# PCB_with_nRF_DUAL_Labeled.net
KiCad netlist of a schematic drawn in EAGLE
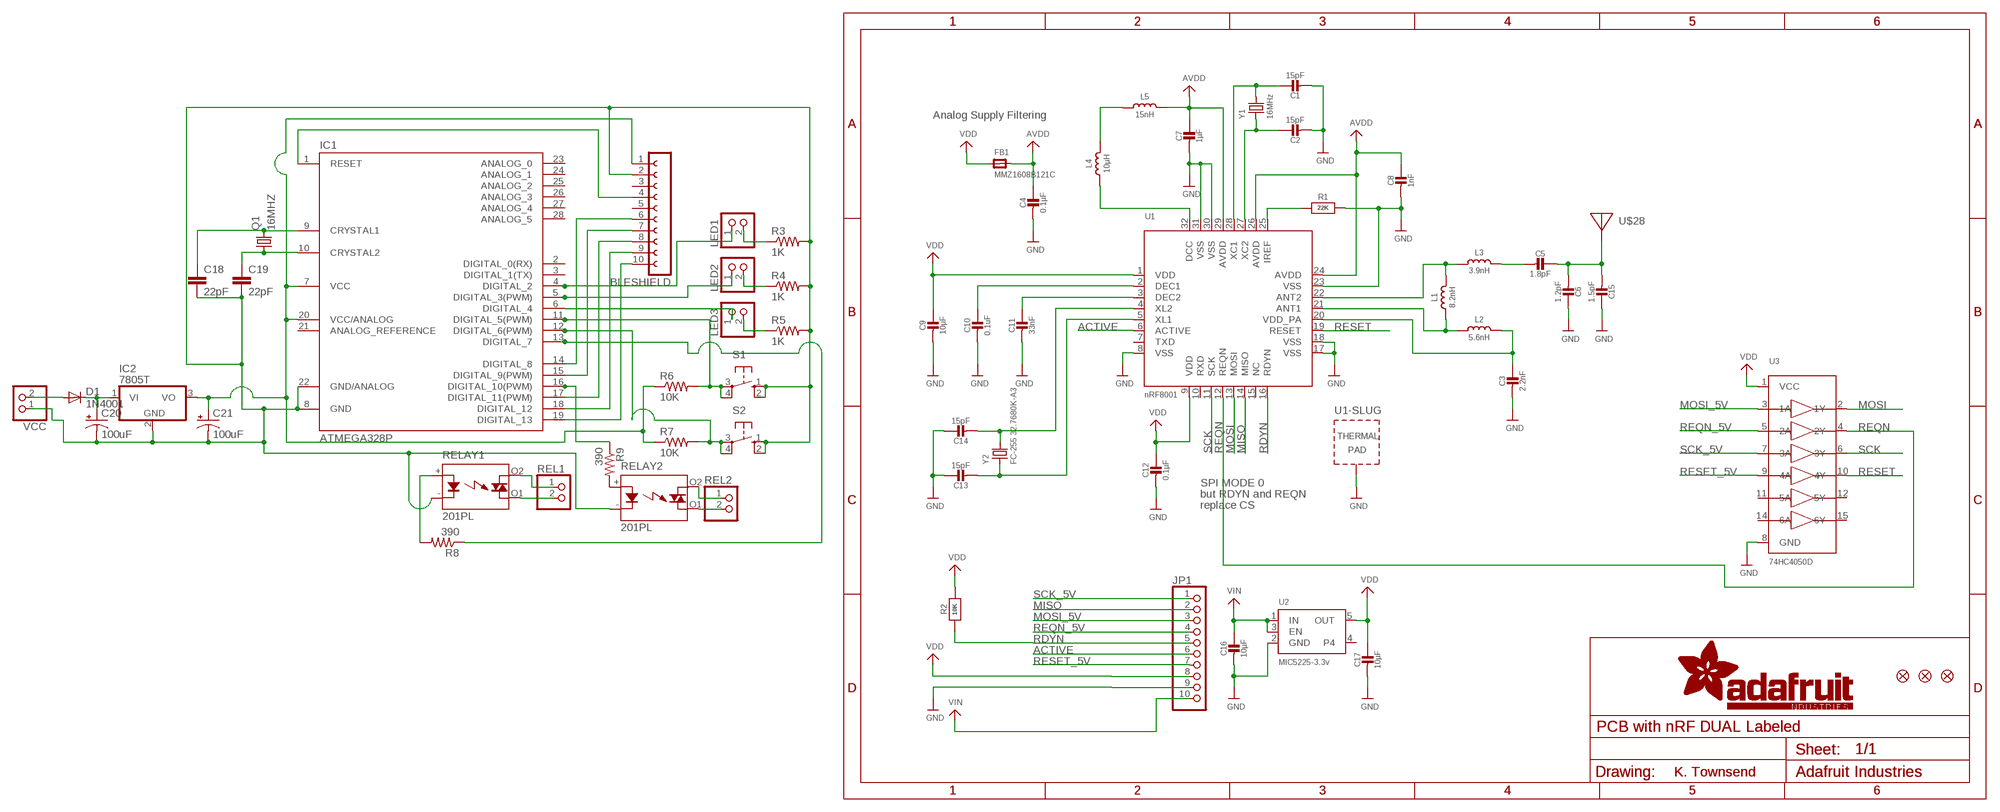
[diagram p0: schematic, sheet 1]

(export (version "E")
  (design (tool "Eeschema 10.0.6"))
  (components
    (comp (ref "BLESHIELD")
      (value "FE10-1")
      (footprint "eagle-import:FE10")
      (libsource (lib "eagle-import") (part "FE10-1"))
    )
    (comp (ref "C1")
      (value "15pF")
      (footprint "eagle-import:0805-NO")
      (libsource (lib "eagle-import") (part "CAP_CERAMIC0805-NOOUTLINE"))
    )
    (comp (ref "C2")
      (value "15pF")
      (footprint "eagle-import:0805-NO")
      (libsource (lib "eagle-import") (part "CAP_CERAMIC0805-NOOUTLINE"))
    )
    (comp (ref "C3")
      (value "2.2nF")
      (footprint "eagle-import:_0402")
      (libsource (lib "eagle-import") (part "CAP_CERAMIC_0402"))
    )
    (comp (ref "C4")
      (value "0.1µF")
      (footprint "eagle-import:0805-NO")
      (libsource (lib "eagle-import") (part "CAP_CERAMIC0805-NOOUTLINE"))
    )
    (comp (ref "C5")
      (value "1.8pF")
      (footprint "eagle-import:_0402MP")
      (libsource (lib "eagle-import") (part "CAP_CERAMIC_0402MP"))
    )
    (comp (ref "C6")
      (value "1.2pF")
      (footprint "eagle-import:_0402MP")
      (libsource (lib "eagle-import") (part "CAP_CERAMIC_0402MP"))
    )
    (comp (ref "C7")
      (value "1µF")
      (footprint "eagle-import:0805-NO")
      (libsource (lib "eagle-import") (part "CAP_CERAMIC0805-NOOUTLINE"))
    )
    (comp (ref "C8")
      (value "1nF")
      (footprint "eagle-import:_0603")
      (libsource (lib "eagle-import") (part "CAP_CERAMIC_0603"))
    )
    (comp (ref "C9")
      (value "10µF")
      (footprint "eagle-import:0805-NO")
      (libsource (lib "eagle-import") (part "CAP_CERAMIC0805-NOOUTLINE"))
    )
    (comp (ref "C10")
      (value "0.1uF")
      (footprint "eagle-import:0805-NO")
      (libsource (lib "eagle-import") (part "CAP_CERAMIC0805-NOOUTLINE"))
    )
    (comp (ref "C11")
      (value "33nF")
      (footprint "eagle-import:0805-NO")
      (libsource (lib "eagle-import") (part "CAP_CERAMIC0805-NOOUTLINE"))
    )
    (comp (ref "C12")
      (value "0.1µF")
      (footprint "eagle-import:0805-NO")
      (libsource (lib "eagle-import") (part "CAP_CERAMIC0805-NOOUTLINE"))
    )
    (comp (ref "C13")
      (value "15pF")
      (footprint "eagle-import:0805-NO")
      (libsource (lib "eagle-import") (part "CAP_CERAMIC0805-NOOUTLINE"))
    )
    (comp (ref "C14")
      (value "15pF")
      (footprint "eagle-import:0805-NO")
      (libsource (lib "eagle-import") (part "CAP_CERAMIC0805-NOOUTLINE"))
    )
    (comp (ref "C15")
      (value "1.5pF")
      (footprint "eagle-import:_0402MP")
      (libsource (lib "eagle-import") (part "CAP_CERAMIC_0402MP"))
    )
    (comp (ref "C16")
      (value "10µF")
      (footprint "eagle-import:0805-NO")
      (libsource (lib "eagle-import") (part "CAP_CERAMIC0805-NOOUTLINE"))
    )
    (comp (ref "C17")
      (value "10µF")
      (footprint "eagle-import:0805-NO")
      (libsource (lib "eagle-import") (part "CAP_CERAMIC0805-NOOUTLINE"))
    )
    (comp (ref "C18")
      (value "22pF")
      (footprint "eagle-import:C025-030X050")
      (libsource (lib "eagle-import") (part "C-EU025-030X050"))
    )
    (comp (ref "C19")
      (value "22pF")
      (footprint "eagle-import:C025-030X050")
      (libsource (lib "eagle-import") (part "C-EU025-030X050"))
    )
    (comp (ref "C20")
      (value "100uF")
      (footprint "eagle-import:E2,5-6")
      (libsource (lib "eagle-import") (part "CPOL-USE2.5-6"))
    )
    (comp (ref "C21")
      (value "100uF")
      (footprint "eagle-import:E2,5-6")
      (libsource (lib "eagle-import") (part "CPOL-USE2.5-6"))
    )
    (comp (ref "D1")
      (value "1N4001")
      (footprint "eagle-import:DO41-10")
      (libsource (lib "eagle-import") (part "1N4004"))
    )
    (comp (ref "FB1")
      (value "MMZ1608B121C")
      (footprint "eagle-import:0805")
      (libsource (lib "eagle-import") (part "FERRITE0805"))
    )
    (comp (ref "FID1")
      (value "FIDUCIAL\"\"")
      (footprint "eagle-import:FIDUCIAL_1MM")
      (libsource (lib "eagle-import") (part "FIDUCIAL{dblquote}{dblquote}"))
    )
    (comp (ref "FID2")
      (value "FIDUCIAL\"\"")
      (footprint "eagle-import:FIDUCIAL_1MM")
      (libsource (lib "eagle-import") (part "FIDUCIAL{dblquote}{dblquote}"))
    )
    (comp (ref "FID3")
      (value "FIDUCIAL\"\"")
      (footprint "eagle-import:FIDUCIAL_1MM")
      (fields (field (name "BOM") "EXCLUDE"))
      (libsource (lib "eagle-import") (part "FIDUCIAL{dblquote}{dblquote}"))
    )
    (comp (ref "IC1")
      (value "ATMEGA328P")
      (footprint "eagle-import:DIL28-3")
      (libsource (lib "eagle-import") (part "ATMEGA168-PU"))
    )
    (comp (ref "IC2")
      (value "7805T")
      (footprint "eagle-import:TO220H")
      (libsource (lib "eagle-import") (part "78T05"))
    )
    (comp (ref "JP1")
      (value "HEADER-1X1070MIL")
      (footprint "eagle-import:1X10_ROUND70")
      (libsource (lib "eagle-import") (part "HEADER-1X1070MIL"))
    )
    (comp (ref "L1")
      (value "8.2nH")
      (footprint "eagle-import:_0402")
      (libsource (lib "eagle-import") (part "INDUCTOR_0402"))
    )
    (comp (ref "L2")
      (value "5.6nH")
      (footprint "eagle-import:_0402")
      (libsource (lib "eagle-import") (part "INDUCTOR_0402"))
    )
    (comp (ref "L3")
      (value "3.9nH")
      (footprint "eagle-import:_0402")
      (libsource (lib "eagle-import") (part "INDUCTOR_0402"))
    )
    (comp (ref "L4")
      (value "10µH")
      (footprint "eagle-import:_0603")
      (libsource (lib "eagle-import") (part "INDUCTOR_0603"))
    )
    (comp (ref "L5")
      (value "15nH")
      (footprint "eagle-import:_0603")
      (libsource (lib "eagle-import") (part "INDUCTOR_0603"))
    )
    (comp (ref "LED1")
      (value "PINHD-1X2")
      (footprint "eagle-import:1X02")
      (libsource (lib "eagle-import") (part "PINHD-1X2"))
    )
    (comp (ref "LED2")
      (value "PINHD-1X2")
      (footprint "eagle-import:1X02")
      (libsource (lib "eagle-import") (part "PINHD-1X2"))
    )
    (comp (ref "LED3")
      (value "PINHD-1X2")
      (footprint "eagle-import:1X02")
      (libsource (lib "eagle-import") (part "PINHD-1X2"))
    )
    (comp (ref "Q1")
      (value "16MHZ")
      (footprint "eagle-import:HC49_S")
      (libsource (lib "eagle-import") (part "CRYSTALHC49S"))
    )
    (comp (ref "R1")
      (value "22K")
      (footprint "eagle-import:_0805MP")
      (libsource (lib "eagle-import") (part "RESISTOR_0805MP"))
    )
    (comp (ref "R2")
      (value "10K")
      (footprint "eagle-import:0805-NO")
      (libsource (lib "eagle-import") (part "RESISTOR0805_NOOUTLINE"))
    )
    (comp (ref "R3")
      (value "1K")
      (footprint "eagle-import:0204_5")
      (libsource (lib "eagle-import") (part "R-US_0204/5"))
    )
    (comp (ref "R4")
      (value "1K")
      (footprint "eagle-import:0204_5")
      (libsource (lib "eagle-import") (part "R-US_0204/5"))
    )
    (comp (ref "R5")
      (value "1K")
      (footprint "eagle-import:0204_5")
      (libsource (lib "eagle-import") (part "R-US_0204/5"))
    )
    (comp (ref "R6")
      (value "10K")
      (footprint "eagle-import:0204_5")
      (libsource (lib "eagle-import") (part "R-US_0204/5"))
    )
    (comp (ref "R7")
      (value "10K")
      (footprint "eagle-import:0204_5")
      (libsource (lib "eagle-import") (part "R-US_0204/5"))
    )
    (comp (ref "R8")
      (value "390")
      (footprint "eagle-import:0204_5")
      (libsource (lib "eagle-import") (part "R-US_0204/5"))
    )
    (comp (ref "R9")
      (value "390")
      (footprint "eagle-import:0204_5")
      (libsource (lib "eagle-import") (part "R-US_0204/5"))
    )
    (comp (ref "REL1")
      (value "PINHD-1X2")
      (footprint "eagle-import:1X02")
      (libsource (lib "eagle-import") (part "PINHD-1X2"))
    )
    (comp (ref "REL2")
      (value "PINHD-1X2")
      (footprint "eagle-import:1X02")
      (libsource (lib "eagle-import") (part "PINHD-1X2"))
    )
    (comp (ref "RELAY1")
      (value "201PL")
      (footprint "eagle-import:AQG")
      (fields (field (name "MF") "AROMAT/ MATSUSHITA") (field (name "MPN") "AQG12105"))
      (libsource (lib "eagle-import") (part "AQG12105"))
    )
    (comp (ref "RELAY2")
      (value "201PL")
      (footprint "eagle-import:AQG")
      (fields (field (name "MF") "AROMAT/ MATSUSHITA") (field (name "MPN") "AQG12105"))
      (libsource (lib "eagle-import") (part "AQG12105"))
    )
    (comp (ref "S1")
      (value "10-XX")
      (footprint "eagle-import:B3F-10XX")
      (fields (field (name "MPN") "B3F-1000"))
      (libsource (lib "eagle-import") (part "10-XX"))
    )
    (comp (ref "S2")
      (value "10-XX")
      (footprint "eagle-import:B3F-10XX")
      (fields (field (name "MPN") "B3F-1000"))
      (libsource (lib "eagle-import") (part "10-XX"))
    )
    (comp (ref "U$28")
      (value "ANTENNA_PCBNRF8001_1.6MM")
      (footprint "eagle-import:ANT_PCB_2.4GHZ_NRF8001_1.6MM_1OZ")
      (libsource (lib "eagle-import") (part "ANTENNA_PCBNRF8001_1.6MM"))
    )
    (comp (ref "U1")
      (value "nRF8001")
      (footprint "eagle-import:QFN32_5MM")
      (libsource (lib "eagle-import") (part "NRF8001"))
    )
    (comp (ref "U2")
      (value "MIC5225-3.3v")
      (footprint "eagle-import:SOT23-5")
      (libsource (lib "eagle-import") (part "VREG_SOT23-5"))
    )
    (comp (ref "U3")
      (value "74HC4050D")
      (footprint "eagle-import:TSSOP16")
      (libsource (lib "eagle-import") (part "74HC4050DTSSOP"))
    )
    (comp (ref "VCC")
      (value "PINHD-1X2")
      (footprint "eagle-import:1X02")
      (libsource (lib "eagle-import") (part "PINHD-1X2"))
    )
    (comp (ref "Y1")
      (value "16MHz")
      (footprint "eagle-import:CRYSTAL_2.5X2")
      (libsource (lib "eagle-import") (part "CRYSTAL2.5X2.0"))
    )
    (comp (ref "Y2")
      (value "FC-255 32.7680K-A3")
      (footprint "eagle-import:CRYSTAL_4.9X1.8")
      (libsource (lib "eagle-import") (part "CRYSTAL4.9X1.8"))
    )
  )
  (nets
    (net (code "1") (name "/ACTIVE") (class "Default")
      (node (ref "JP1") (pin "6") (pinfunction "6_6") (pintype "passive"))
      (node (ref "U1") (pin "6") (pinfunction "ACTIVE_6") (pintype "output"))
    )
    (net (code "2") (name "/MISO") (class "Default")
      (node (ref "JP1") (pin "2") (pinfunction "2_2") (pintype "passive"))
      (node (ref "U1") (pin "14") (pinfunction "MISO_14") (pintype "output"))
    )
    (net (code "3") (name "/MOSI") (class "Default")
      (node (ref "U1") (pin "13") (pinfunction "MOSI_13") (pintype "input"))
      (node (ref "U3") (pin "2") (pinfunction "1Y_2") (pintype "bidirectional"))
    )
    (net (code "4") (name "/MOSI_5V") (class "Default")
      (node (ref "JP1") (pin "3") (pinfunction "3_3") (pintype "passive"))
      (node (ref "U3") (pin "3") (pinfunction "1A_3") (pintype "bidirectional"))
    )
    (net (code "5") (name "/RDYN") (class "Default")
      (node (ref "JP1") (pin "5") (pinfunction "5_5") (pintype "passive"))
      (node (ref "R2") (pin "1") (pinfunction "1_1") (pintype "passive"))
      (node (ref "U1") (pin "16") (pinfunction "RDYN_16") (pintype "output"))
    )
    (net (code "6") (name "/REQN") (class "Default")
      (node (ref "U1") (pin "12") (pinfunction "REQN_12") (pintype "input"))
      (node (ref "U3") (pin "4") (pinfunction "2Y_4") (pintype "bidirectional"))
    )
    (net (code "7") (name "/REQN_5V") (class "Default")
      (node (ref "JP1") (pin "4") (pinfunction "4_4") (pintype "passive"))
      (node (ref "U3") (pin "5") (pinfunction "2A_5") (pintype "bidirectional"))
    )
    (net (code "8") (name "/RESET") (class "Default")
      (node (ref "U1") (pin "19") (pinfunction "RESET_19") (pintype "input"))
      (node (ref "U3") (pin "10") (pinfunction "4Y_10") (pintype "bidirectional"))
    )
    (net (code "9") (name "/RESET_5V") (class "Default")
      (node (ref "JP1") (pin "7") (pinfunction "7_7") (pintype "passive"))
      (node (ref "U3") (pin "9") (pinfunction "4A_9") (pintype "bidirectional"))
    )
    (net (code "10") (name "/SCK") (class "Default")
      (node (ref "U1") (pin "11") (pinfunction "SCK_11") (pintype "input"))
      (node (ref "U3") (pin "6") (pinfunction "3Y_6") (pintype "bidirectional"))
    )
    (net (code "11") (name "/SCK_5V") (class "Default")
      (node (ref "JP1") (pin "1") (pinfunction "1_1") (pintype "passive"))
      (node (ref "U3") (pin "7") (pinfunction "3A_7") (pintype "bidirectional"))
    )
    (net (code "12") (name "AVDD") (class "Default")
      (node (ref "C4") (pin "1") (pinfunction "1_1") (pintype "passive"))
      (node (ref "C7") (pin "1") (pinfunction "1_1") (pintype "passive"))
      (node (ref "C8") (pin "1") (pinfunction "1_1") (pintype "passive"))
      (node (ref "FB1") (pin "2") (pinfunction "P$2_2") (pintype "passive"))
      (node (ref "L5") (pin "2") (pinfunction "2_2") (pintype "passive"))
      (node (ref "U1") (pin "24") (pinfunction "AVDD_24") (pintype "power_in"))
      (node (ref "U1") (pin "26") (pinfunction "AVDD_26") (pintype "power_in"))
      (node (ref "U1") (pin "29") (pinfunction "AVDD_29") (pintype "power_in"))
    )
    (net (code "13") (name "GND") (class "Default")
      (node (ref "C1") (pin "2") (pinfunction "2_2") (pintype "passive"))
      (node (ref "C10") (pin "2") (pinfunction "2_2") (pintype "passive"))
      (node (ref "C11") (pin "2") (pinfunction "2_2") (pintype "passive"))
      (node (ref "C12") (pin "2") (pinfunction "2_2") (pintype "passive"))
      (node (ref "C13") (pin "1") (pinfunction "1_1") (pintype "passive"))
      (node (ref "C14") (pin "1") (pinfunction "1_1") (pintype "passive"))
      (node (ref "C15") (pin "1") (pinfunction "1_1") (pintype "passive"))
      (node (ref "C16") (pin "2") (pinfunction "2_2") (pintype "passive"))
      (node (ref "C17") (pin "2") (pinfunction "2_2") (pintype "passive"))
      (node (ref "C2") (pin "2") (pinfunction "2_2") (pintype "passive"))
      (node (ref "C3") (pin "2") (pinfunction "2_2") (pintype "passive"))
      (node (ref "C4") (pin "2") (pinfunction "2_2") (pintype "passive"))
      (node (ref "C6") (pin "1") (pinfunction "1_1") (pintype "passive"))
      (node (ref "C7") (pin "2") (pinfunction "2_2") (pintype "passive"))
      (node (ref "C8") (pin "2") (pinfunction "2_2") (pintype "passive"))
      (node (ref "C9") (pin "2") (pinfunction "2_2") (pintype "passive"))
      (node (ref "JP1") (pin "9") (pinfunction "9_9") (pintype "passive"))
      (node (ref "R1") (pin "2") (pinfunction "2_2") (pintype "passive"))
      (node (ref "U1") (pin "17") (pinfunction "VSS_17") (pintype "power_in"))
      (node (ref "U1") (pin "18") (pinfunction "VSS_18") (pintype "power_in"))
      (node (ref "U1") (pin "23") (pinfunction "VSS_23") (pintype "power_in"))
      (node (ref "U1") (pin "30") (pinfunction "VSS_30") (pintype "power_in"))
      (node (ref "U1") (pin "31") (pinfunction "VSS_31") (pintype "power_in"))
      (node (ref "U1") (pin "33") (pinfunction "TP_33") (pintype "power_in"))
      (node (ref "U1") (pin "8") (pinfunction "VSS_8") (pintype "power_in"))
      (node (ref "U2") (pin "2") (pinfunction "GND_2") (pintype "power_in"))
      (node (ref "U3") (pin "8") (pinfunction "GND_8") (pintype "bidirectional"))
    )
    (net (code "14") (name "Net-(C5-Pad2)") (class "Default")
      (node (ref "C5") (pin "2") (pinfunction "2_2") (pintype "passive"))
      (node (ref "L3") (pin "2") (pinfunction "2_2") (pintype "passive"))
    )
    (net (code "15") (name "Net-(D1-PadA)") (class "Default")
      (node (ref "D1") (pin "A") (pinfunction "A_A") (pintype "passive"))
      (node (ref "VCC") (pin "2") (pinfunction "2_2") (pintype "passive"))
    )
    (net (code "16") (name "Net-(IC1-CRYSTAL1)") (class "Default")
      (node (ref "C18") (pin "1") (pinfunction "1_1") (pintype "passive"))
      (node (ref "IC1") (pin "9") (pinfunction "CRYSTAL1_9") (pintype "bidirectional"))
      (node (ref "Q1") (pin "2") (pinfunction "2_2") (pintype "passive"))
    )
    (net (code "17") (name "Net-(IC1-CRYSTAL2)") (class "Default")
      (node (ref "C19") (pin "1") (pinfunction "1_1") (pintype "passive"))
      (node (ref "IC1") (pin "10") (pinfunction "CRYSTAL2_10") (pintype "bidirectional"))
      (node (ref "Q1") (pin "1") (pinfunction "1_1") (pintype "passive"))
    )
    (net (code "18") (name "Net-(IC1-DIGITAL_2)") (class "Default")
      (node (ref "IC1") (pin "4") (pinfunction "DIGITAL_2_4") (pintype "bidirectional"))
      (node (ref "LED1") (pin "1") (pinfunction "1_1") (pintype "passive"))
    )
    (net (code "19") (name "Net-(IC1-DIGITAL_3(PWM))") (class "Default")
      (node (ref "IC1") (pin "5") (pinfunction "DIGITAL_3(PWM)_5") (pintype "bidirectional"))
      (node (ref "LED2") (pin "1") (pinfunction "1_1") (pintype "passive"))
    )
    (net (code "20") (name "Net-(IC1-DIGITAL_4)") (class "Default")
      (node (ref "IC1") (pin "6") (pinfunction "DIGITAL_4_6") (pintype "bidirectional"))
      (node (ref "LED3") (pin "1") (pinfunction "1_1") (pintype "passive"))
    )
    (net (code "21") (name "Net-(IC1-DIGITAL_5(PWM))") (class "Default")
      (node (ref "IC1") (pin "11") (pinfunction "DIGITAL_5(PWM)_11") (pintype "bidirectional"))
      (node (ref "R6") (pin "2") (pinfunction "2_2") (pintype "passive"))
      (node (ref "S1") (pin "3") (pinfunction "P_3") (pintype "passive"))
      (node (ref "S1") (pin "4") (pinfunction "P1_4") (pintype "passive"))
    )
    (net (code "22") (name "Net-(IC1-DIGITAL_6(PWM))") (class "Default")
      (node (ref "IC1") (pin "12") (pinfunction "DIGITAL_6(PWM)_12") (pintype "bidirectional"))
      (node (ref "R7") (pin "2") (pinfunction "2_2") (pintype "passive"))
      (node (ref "S2") (pin "3") (pinfunction "P_3") (pintype "passive"))
      (node (ref "S2") (pin "4") (pinfunction "P1_4") (pintype "passive"))
    )
    (net (code "23") (name "Net-(IC1-DIGITAL_7)") (class "Default")
      (node (ref "IC1") (pin "13") (pinfunction "DIGITAL_7_13") (pintype "bidirectional"))
      (node (ref "R8") (pin "1") (pinfunction "1_1") (pintype "passive"))
    )
    (net (code "24") (name "Net-(IC1-DIGITAL_8)") (class "Default")
      (node (ref "BLESHIELD") (pin "6") (pinfunction "6_6") (pintype "passive"))
      (node (ref "IC1") (pin "14") (pinfunction "DIGITAL_8_14") (pintype "bidirectional"))
    )
    (net (code "25") (name "Net-(IC1-DIGITAL_9(PWM))") (class "Default")
      (node (ref "BLESHIELD") (pin "7") (pinfunction "7_7") (pintype "passive"))
      (node (ref "IC1") (pin "15") (pinfunction "DIGITAL_9(PWM)_15") (pintype "bidirectional"))
    )
    (net (code "26") (name "Net-(IC1-DIGITAL_10(PWM))") (class "Default")
      (node (ref "IC1") (pin "16") (pinfunction "DIGITAL_10(PWM)_16") (pintype "bidirectional"))
      (node (ref "R9") (pin "1") (pinfunction "1_1") (pintype "passive"))
    )
    (net (code "27") (name "Net-(IC1-DIGITAL_11(PWM))") (class "Default")
      (node (ref "BLESHIELD") (pin "8") (pinfunction "8_8") (pintype "passive"))
      (node (ref "IC1") (pin "17") (pinfunction "DIGITAL_11(PWM)_17") (pintype "bidirectional"))
    )
    (net (code "28") (name "Net-(IC1-DIGITAL_12)") (class "Default")
      (node (ref "BLESHIELD") (pin "9") (pinfunction "9_9") (pintype "passive"))
      (node (ref "IC1") (pin "18") (pinfunction "DIGITAL_12_18") (pintype "bidirectional"))
    )
    (net (code "29") (name "Net-(IC1-DIGITAL_13)") (class "Default")
      (node (ref "BLESHIELD") (pin "10") (pinfunction "10_10") (pintype "passive"))
      (node (ref "IC1") (pin "19") (pinfunction "DIGITAL_13_19") (pintype "bidirectional"))
    )
    (net (code "30") (name "Net-(IC1-GND)") (class "Default")
      (node (ref "BLESHIELD") (pin "2") (pinfunction "2_2") (pintype "passive"))
      (node (ref "C18") (pin "2") (pinfunction "2_2") (pintype "passive"))
      (node (ref "C19") (pin "2") (pinfunction "2_2") (pintype "passive"))
      (node (ref "C20") (pin "-") (pinfunction "-_-") (pintype "passive"))
      (node (ref "C21") (pin "-") (pinfunction "-_-") (pintype "passive"))
      (node (ref "IC1") (pin "22") (pinfunction "GND/ANALOG_22") (pintype "power_in"))
      (node (ref "IC1") (pin "8") (pinfunction "GND_8") (pintype "power_in"))
      (node (ref "IC2") (pin "2") (pinfunction "GND_2") (pintype "passive"))
      (node (ref "R3") (pin "2") (pinfunction "2_2") (pintype "passive"))
      (node (ref "R4") (pin "2") (pinfunction "2_2") (pintype "passive"))
      (node (ref "R5") (pin "2") (pinfunction "2_2") (pintype "passive"))
      (node (ref "RELAY1") (pin "-") (pinfunction "K_-") (pintype "passive"))
      (node (ref "RELAY2") (pin "-") (pinfunction "K_-") (pintype "passive"))
      (node (ref "S1") (pin "1") (pinfunction "S_1") (pintype "passive"))
      (node (ref "S1") (pin "2") (pinfunction "S1_2") (pintype "passive"))
      (node (ref "S2") (pin "1") (pinfunction "S_1") (pintype "passive"))
      (node (ref "S2") (pin "2") (pinfunction "S1_2") (pintype "passive"))
      (node (ref "VCC") (pin "1") (pinfunction "1_1") (pintype "passive"))
    )
    (net (code "31") (name "Net-(IC1-RESET)") (class "Default")
      (node (ref "BLESHIELD") (pin "4") (pinfunction "4_4") (pintype "passive"))
      (node (ref "IC1") (pin "1") (pinfunction "RESET_1") (pintype "bidirectional"))
    )
    (net (code "32") (name "Net-(IC1-VCC)") (class "Default")
      (node (ref "BLESHIELD") (pin "1") (pinfunction "1_1") (pintype "passive"))
      (node (ref "C21") (pin "+") (pinfunction "+_+") (pintype "passive"))
      (node (ref "IC1") (pin "20") (pinfunction "VCC/ANALOG_20") (pintype "passive"))
      (node (ref "IC1") (pin "7") (pinfunction "VCC_7") (pintype "power_in"))
      (node (ref "IC2") (pin "3") (pinfunction "VO_3") (pintype "passive"))
      (node (ref "R6") (pin "1") (pinfunction "1_1") (pintype "passive"))
      (node (ref "R7") (pin "1") (pinfunction "1_1") (pintype "passive"))
    )
    (net (code "33") (name "Net-(IC2-VI)") (class "Default")
      (node (ref "C20") (pin "+") (pinfunction "+_+") (pintype "passive"))
      (node (ref "D1") (pin "C") (pinfunction "C_C") (pintype "passive"))
      (node (ref "IC2") (pin "1") (pinfunction "VI_1") (pintype "input"))
    )
    (net (code "34") (name "Net-(L4-Pad2)") (class "Default")
      (node (ref "L4") (pin "2") (pinfunction "2_2") (pintype "passive"))
      (node (ref "L5") (pin "1") (pinfunction "1_1") (pintype "passive"))
    )
    (net (code "35") (name "Net-(LED1-Pad2)") (class "Default")
      (node (ref "LED1") (pin "2") (pinfunction "2_2") (pintype "passive"))
      (node (ref "R3") (pin "1") (pinfunction "1_1") (pintype "passive"))
    )
    (net (code "36") (name "Net-(LED2-Pad2)") (class "Default")
      (node (ref "LED2") (pin "2") (pinfunction "2_2") (pintype "passive"))
      (node (ref "R4") (pin "1") (pinfunction "1_1") (pintype "passive"))
    )
    (net (code "37") (name "Net-(LED3-Pad2)") (class "Default")
      (node (ref "LED3") (pin "2") (pinfunction "2_2") (pintype "passive"))
      (node (ref "R5") (pin "1") (pinfunction "1_1") (pintype "passive"))
    )
    (net (code "38") (name "Net-(RELAY1-A)") (class "Default")
      (node (ref "R8") (pin "2") (pinfunction "2_2") (pintype "passive"))
      (node (ref "RELAY1") (pin "+") (pinfunction "A_+") (pintype "passive"))
    )
    (net (code "39") (name "Net-(RELAY1-DS1)") (class "Default")
      (node (ref "REL1") (pin "1") (pinfunction "1_1") (pintype "passive"))
      (node (ref "RELAY1") (pin "O2") (pinfunction "DS1_O2") (pintype "passive"))
    )
    (net (code "40") (name "Net-(RELAY1-DS2)") (class "Default")
      (node (ref "REL1") (pin "2") (pinfunction "2_2") (pintype "passive"))
      (node (ref "RELAY1") (pin "O1") (pinfunction "DS2_O1") (pintype "passive"))
    )
    (net (code "41") (name "Net-(RELAY2-A)") (class "Default")
      (node (ref "R9") (pin "2") (pinfunction "2_2") (pintype "passive"))
      (node (ref "RELAY2") (pin "+") (pinfunction "A_+") (pintype "passive"))
    )
    (net (code "42") (name "Net-(RELAY2-DS1)") (class "Default")
      (node (ref "REL2") (pin "1") (pinfunction "1_1") (pintype "passive"))
      (node (ref "RELAY2") (pin "O2") (pinfunction "DS1_O2") (pintype "passive"))
    )
    (net (code "43") (name "Net-(RELAY2-DS2)") (class "Default")
      (node (ref "REL2") (pin "2") (pinfunction "2_2") (pintype "passive"))
      (node (ref "RELAY2") (pin "O1") (pinfunction "DS2_O1") (pintype "passive"))
    )
    (net (code "44") (name "Net-(U$28-P$1)") (class "Default")
      (node (ref "C15") (pin "2") (pinfunction "2_2") (pintype "passive"))
      (node (ref "C5") (pin "1") (pinfunction "1_1") (pintype "passive"))
      (node (ref "C6") (pin "2") (pinfunction "2_2") (pintype "passive"))
      (node (ref "U$28") (pin "FEED") (pinfunction "P$1_FEED") (pintype "passive"))
    )
    (net (code "45") (name "Net-(U1B-ANT1)") (class "Default")
      (node (ref "L1") (pin "1") (pinfunction "1_1") (pintype "passive"))
      (node (ref "L2") (pin "1") (pinfunction "1_1") (pintype "passive"))
      (node (ref "U1") (pin "21") (pinfunction "ANT1_21") (pintype "bidirectional"))
    )
    (net (code "46") (name "Net-(U1B-ANT2)") (class "Default")
      (node (ref "L1") (pin "2") (pinfunction "2_2") (pintype "passive"))
      (node (ref "L3") (pin "1") (pinfunction "1_1") (pintype "passive"))
      (node (ref "U1") (pin "22") (pinfunction "ANT2_22") (pintype "bidirectional"))
    )
    (net (code "47") (name "Net-(U1B-DCC)") (class "Default")
      (node (ref "L4") (pin "1") (pinfunction "1_1") (pintype "passive"))
      (node (ref "U1") (pin "32") (pinfunction "DCC_32") (pintype "bidirectional"))
    )
    (net (code "48") (name "Net-(U1B-DEC1)") (class "Default")
      (node (ref "C10") (pin "1") (pinfunction "1_1") (pintype "passive"))
      (node (ref "U1") (pin "2") (pinfunction "DEC1_2") (pintype "bidirectional"))
    )
    (net (code "49") (name "Net-(U1B-DEC2)") (class "Default")
      (node (ref "C11") (pin "1") (pinfunction "1_1") (pintype "passive"))
      (node (ref "U1") (pin "3") (pinfunction "DEC2_3") (pintype "bidirectional"))
    )
    (net (code "50") (name "Net-(U1B-IREF)") (class "Default")
      (node (ref "R1") (pin "1") (pinfunction "1_1") (pintype "passive"))
      (node (ref "U1") (pin "25") (pinfunction "IREF_25") (pintype "output"))
    )
    (net (code "51") (name "Net-(U1B-VDD_PA)") (class "Default")
      (node (ref "C3") (pin "1") (pinfunction "1_1") (pintype "passive"))
      (node (ref "L2") (pin "2") (pinfunction "2_2") (pintype "passive"))
      (node (ref "U1") (pin "20") (pinfunction "VDD_PA_20") (pintype "bidirectional"))
    )
    (net (code "52") (name "Net-(U1B-XC1)") (class "Default")
      (node (ref "C1") (pin "1") (pinfunction "1_1") (pintype "passive"))
      (node (ref "U1") (pin "28") (pinfunction "XC1_28") (pintype "input"))
      (node (ref "Y1") (pin "3") (pinfunction "2_3") (pintype "passive"))
    )
    (net (code "53") (name "Net-(U1B-XC2)") (class "Default")
      (node (ref "C2") (pin "1") (pinfunction "1_1") (pintype "passive"))
      (node (ref "U1") (pin "27") (pinfunction "XC2_27") (pintype "output"))
      (node (ref "Y1") (pin "1") (pinfunction "1_1") (pintype "passive"))
    )
    (net (code "54") (name "Net-(U1B-XL1)") (class "Default")
      (node (ref "C13") (pin "2") (pinfunction "2_2") (pintype "passive"))
      (node (ref "U1") (pin "5") (pinfunction "XL1_5") (pintype "input"))
      (node (ref "Y2") (pin "1") (pinfunction "1_1") (pintype "passive"))
    )
    (net (code "55") (name "Net-(U1B-XL2)") (class "Default")
      (node (ref "C14") (pin "2") (pinfunction "2_2") (pintype "passive"))
      (node (ref "U1") (pin "4") (pinfunction "XL2_4") (pintype "output"))
      (node (ref "Y2") (pin "2") (pinfunction "2_2") (pintype "passive"))
    )
    (net (code "56") (name "VDD") (class "Default")
      (node (ref "C12") (pin "1") (pinfunction "1_1") (pintype "passive"))
      (node (ref "C17") (pin "1") (pinfunction "1_1") (pintype "passive"))
      (node (ref "C9") (pin "1") (pinfunction "1_1") (pintype "passive"))
      (node (ref "FB1") (pin "1") (pinfunction "P$1_1") (pintype "passive"))
      (node (ref "JP1") (pin "8") (pinfunction "8_8") (pintype "passive"))
      (node (ref "R2") (pin "2") (pinfunction "2_2") (pintype "passive"))
      (node (ref "U1") (pin "1") (pinfunction "VDD_1") (pintype "power_in"))
      (node (ref "U1") (pin "9") (pinfunction "VDD_9") (pintype "power_in"))
      (node (ref "U2") (pin "5") (pinfunction "OUT_5") (pintype "power_in"))
      (node (ref "U3") (pin "1") (pinfunction "VCC_1") (pintype "bidirectional"))
    )
    (net (code "57") (name "VIN") (class "Default")
      (node (ref "C16") (pin "1") (pinfunction "1_1") (pintype "passive"))
      (node (ref "JP1") (pin "10") (pinfunction "10_10") (pintype "passive"))
      (node (ref "U2") (pin "1") (pinfunction "IN_1") (pintype "power_in"))
      (node (ref "U2") (pin "3") (pinfunction "EN_3") (pintype "input"))
    )
    (net (code "58") (name "unconnected-(BLESHIELD-Pad3)") (class "Default")
      (node (ref "BLESHIELD") (pin "3") (pinfunction "3_3") (pintype "passive"))
    )
    (net (code "59") (name "unconnected-(BLESHIELD-Pad5)") (class "Default")
      (node (ref "BLESHIELD") (pin "5") (pinfunction "5_5") (pintype "passive"))
    )
    (net (code "60") (name "unconnected-(IC1-ANALOG_0-Pad23)") (class "Default")
      (node (ref "IC1") (pin "23") (pinfunction "ANALOG_0_23") (pintype "bidirectional"))
    )
    (net (code "61") (name "unconnected-(IC1-ANALOG_1-Pad24)") (class "Default")
      (node (ref "IC1") (pin "24") (pinfunction "ANALOG_1_24") (pintype "bidirectional"))
    )
    (net (code "62") (name "unconnected-(IC1-ANALOG_2-Pad25)") (class "Default")
      (node (ref "IC1") (pin "25") (pinfunction "ANALOG_2_25") (pintype "bidirectional"))
    )
    (net (code "63") (name "unconnected-(IC1-ANALOG_3-Pad26)") (class "Default")
      (node (ref "IC1") (pin "26") (pinfunction "ANALOG_3_26") (pintype "bidirectional"))
    )
    (net (code "64") (name "unconnected-(IC1-ANALOG_4-Pad27)") (class "Default")
      (node (ref "IC1") (pin "27") (pinfunction "ANALOG_4_27") (pintype "bidirectional"))
    )
    (net (code "65") (name "unconnected-(IC1-ANALOG_5-Pad28)") (class "Default")
      (node (ref "IC1") (pin "28") (pinfunction "ANALOG_5_28") (pintype "bidirectional"))
    )
    (net (code "66") (name "unconnected-(IC1-ANALOG_REFERENCE-Pad21)") (class "Default")
      (node (ref "IC1") (pin "21") (pinfunction "ANALOG_REFERENCE_21") (pintype "passive"))
    )
    (net (code "67") (name "unconnected-(IC1-DIGITAL_0(RX)-Pad2)") (class "Default")
      (node (ref "IC1") (pin "2") (pinfunction "DIGITAL_0(RX)_2") (pintype "bidirectional"))
    )
    (net (code "68") (name "unconnected-(IC1-DIGITAL_1(TX)-Pad3)") (class "Default")
      (node (ref "IC1") (pin "3") (pinfunction "DIGITAL_1(TX)_3") (pintype "bidirectional"))
    )
    (net (code "69") (name "unconnected-(U1B-NC-Pad15)") (class "Default")
      (node (ref "U1") (pin "15") (pinfunction "NC_15") (pintype "no_connect"))
    )
    (net (code "70") (name "unconnected-(U1B-RXD-Pad10)") (class "Default")
      (node (ref "U1") (pin "10") (pinfunction "RXD_10") (pintype "input"))
    )
    (net (code "71") (name "unconnected-(U1B-TXD-Pad7)") (class "Default")
      (node (ref "U1") (pin "7") (pinfunction "TXD_7") (pintype "output"))
    )
    (net (code "72") (name "unconnected-(U2-P4-Pad4)") (class "Default")
      (node (ref "U2") (pin "4") (pinfunction "P4_4") (pintype "bidirectional"))
    )
    (net (code "73") (name "unconnected-(U3-5A-Pad11)") (class "Default")
      (node (ref "U3") (pin "11") (pinfunction "5A_11") (pintype "bidirectional"))
    )
    (net (code "74") (name "unconnected-(U3-5Y-Pad12)") (class "Default")
      (node (ref "U3") (pin "12") (pinfunction "5Y_12") (pintype "bidirectional"))
    )
    (net (code "75") (name "unconnected-(U3-6A-Pad14)") (class "Default")
      (node (ref "U3") (pin "14") (pinfunction "6A_14") (pintype "bidirectional"))
    )
    (net (code "76") (name "unconnected-(U3-6Y-Pad15)") (class "Default")
      (node (ref "U3") (pin "15") (pinfunction "6Y_15") (pintype "bidirectional"))
    )
  )
)
